# VL53L1X.net
KiCad netlist of a schematic drawn in Altium Designer
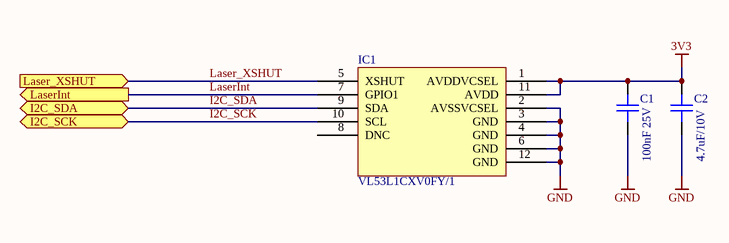
[diagram p0: VL53L1X.SchDoc]

(export (version "E")
  (design (tool "Eeschema 10.0.6"))
  (components
    (comp (ref "C1")
      (value "100nF 25V")
      (footprint "C0402")
      (description "WALSIN - 0402B104K250CT - CAPACITOR, MLCC, X7R, 0.1UF, 25V, 0402")
      (fields (field (name "Comment") "UniversalCapacitor"))
      (libsource (lib "UTBStockLib") (part "UniversalCapacitor"))
    )
    (comp (ref "C2")
      (value "4.7uF/10V")
      (footprint "C0402_big")
      (description "MURATA - GRM155R61A475MEAAD - CAP, MLCC, X5R, 4.7UF, 10V, 0402")
      (libsource (lib "UTBStockLib") (part "UniversalCapacitor"))
    )
    (comp (ref "IC1")
      (value "VL53L1CXV0FY/1")
      (footprint "VL53L1X")
      (description "STMICROELECTRONICS - VL53L1CXV0FY/1 - Proximity Sensor, I2C, 4000 mm, OLGA, 12 Pins, 2.6 V, 3.5 V")
      (fields (field (name "Comment") "VL53L1X"))
      (libsource (lib "UTBStockLib") (part "VL53L1X"))
    )
  )
  (nets
    (net (code "1") (name "/I2C_SCK") (class "Default")
      (node (ref "IC1") (pin "10") (pinfunction "SCL_10") (pintype "passive"))
    )
    (net (code "2") (name "/I2C_SDA") (class "Default")
      (node (ref "IC1") (pin "9") (pinfunction "SDA_9") (pintype "passive"))
    )
    (net (code "3") (name "/LaserInt") (class "Default")
      (node (ref "IC1") (pin "7") (pinfunction "GPIO1_7") (pintype "passive"))
    )
    (net (code "4") (name "/Laser_XSHUT") (class "Default")
      (node (ref "IC1") (pin "5") (pinfunction "XSHUT_5") (pintype "passive"))
    )
    (net (code "5") (name "3V3") (class "Default")
      (node (ref "C1") (pin "2") (pinfunction "2_2") (pintype "passive"))
      (node (ref "C2") (pin "1") (pinfunction "1_1") (pintype "passive"))
      (node (ref "IC1") (pin "1") (pinfunction "AVDDVCSEL_1") (pintype "passive"))
      (node (ref "IC1") (pin "11") (pinfunction "AVDD_11") (pintype "passive"))
    )
    (net (code "6") (name "GND") (class "Default")
      (node (ref "C1") (pin "1") (pinfunction "1_1") (pintype "passive"))
      (node (ref "C2") (pin "2") (pinfunction "2_2") (pintype "passive"))
      (node (ref "IC1") (pin "12") (pinfunction "GND_12") (pintype "passive"))
      (node (ref "IC1") (pin "2") (pinfunction "AVSSVCSEL_2") (pintype "passive"))
      (node (ref "IC1") (pin "3") (pinfunction "GND_3") (pintype "passive"))
      (node (ref "IC1") (pin "4") (pinfunction "GND_4") (pintype "passive"))
      (node (ref "IC1") (pin "6") (pinfunction "GND_6") (pintype "passive"))
    )
    (net (code "7") (name "unconnected-(IC1-DNC-Pad8)") (class "Default")
      (node (ref "IC1") (pin "8") (pinfunction "DNC_8") (pintype "passive"))
    )
  )
)
